# polarshield3_0d.net
KiCad netlist of a schematic drawn in EAGLE
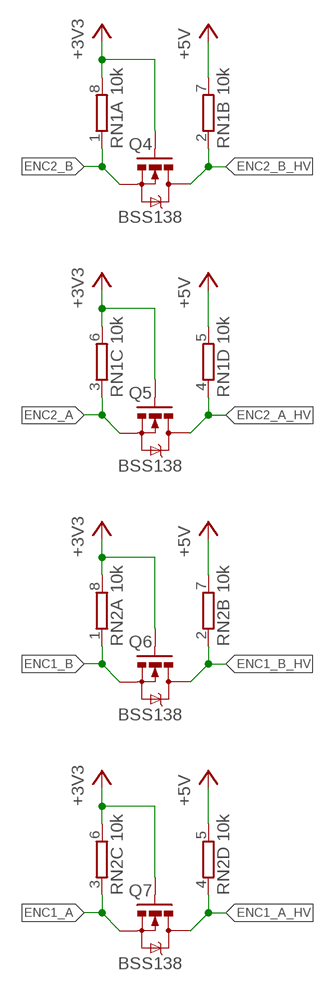
[diagram p0: schematic, sheet 1, part 1 of 2]
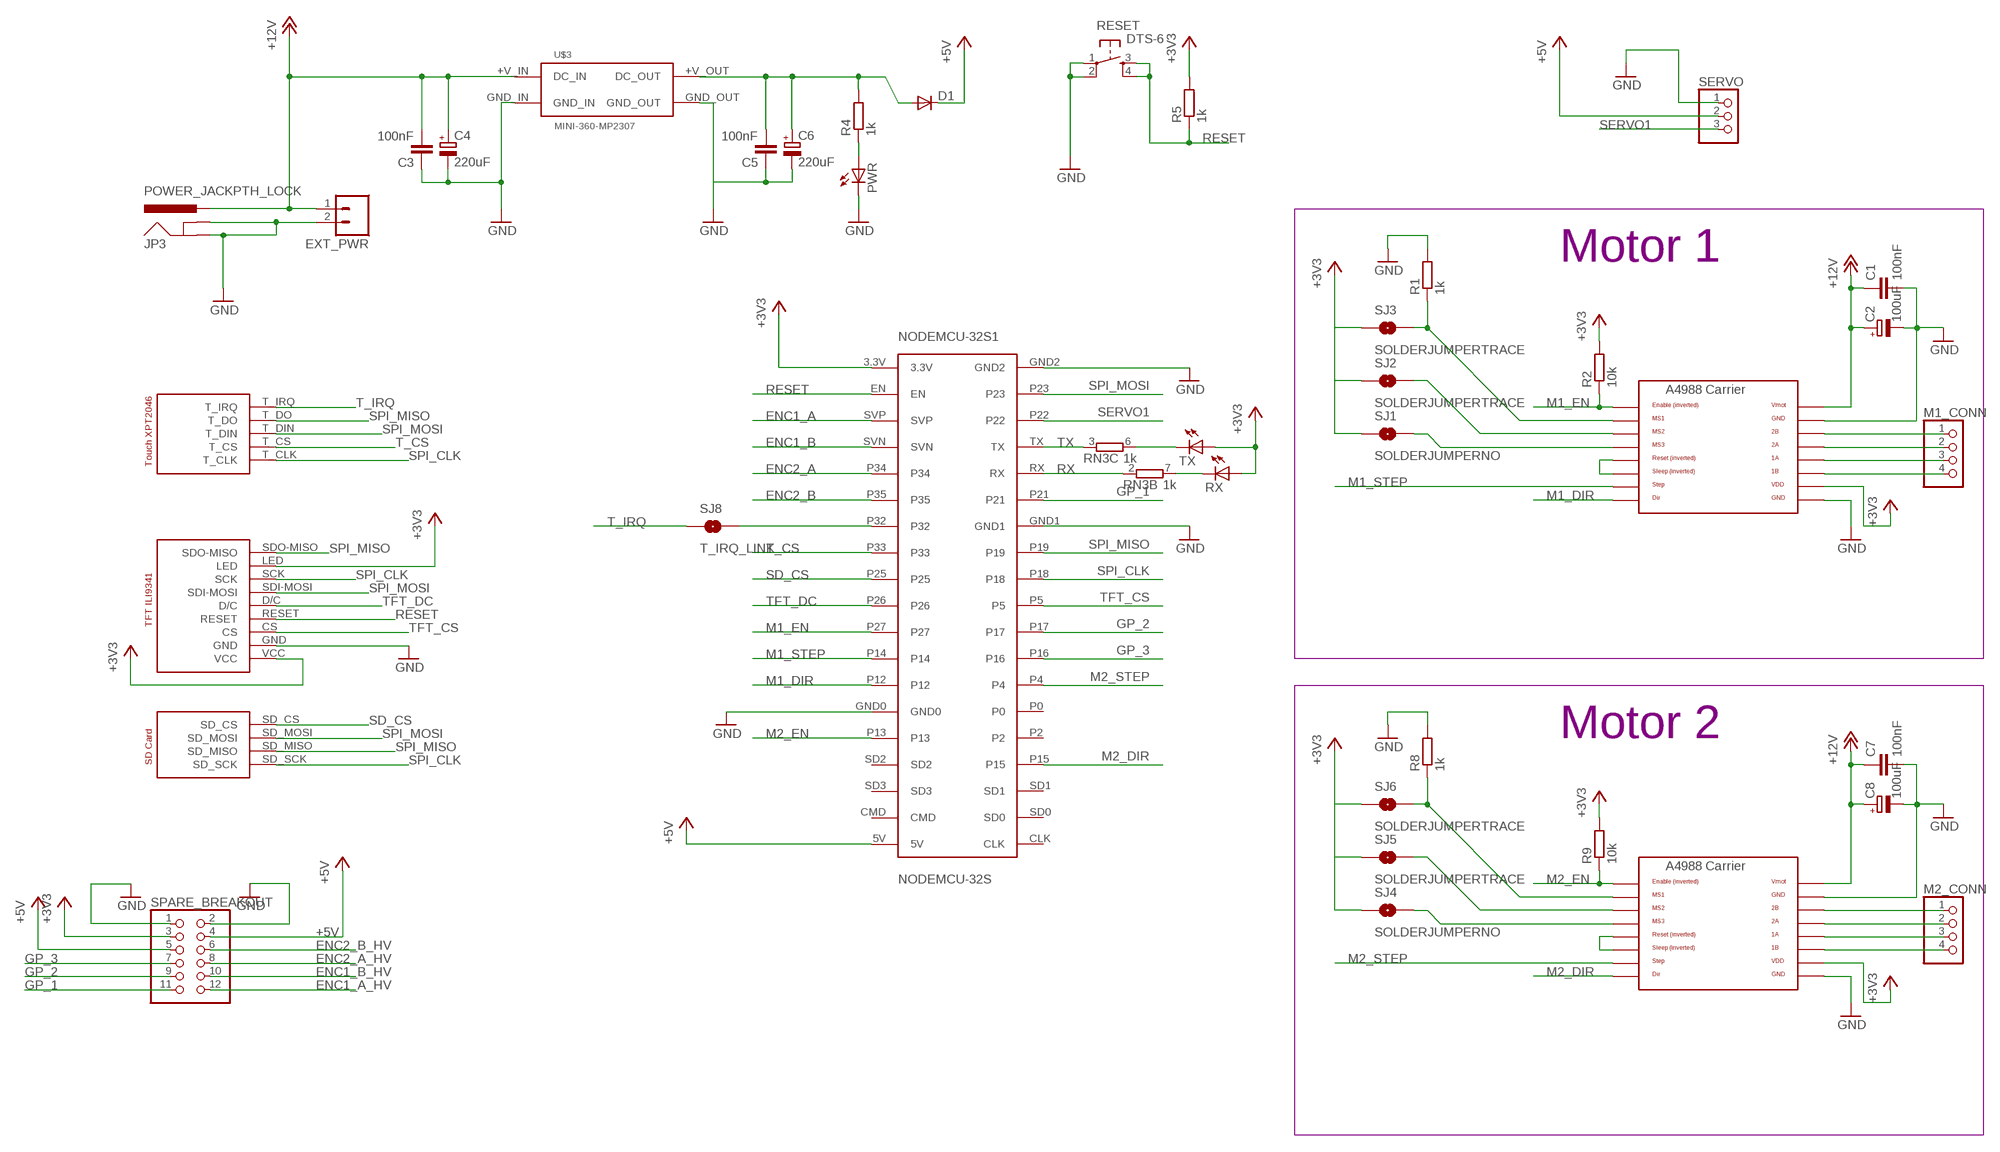
[diagram p1: schematic, sheet 1, part 2 of 2]

(export (version "E")
  (design (tool "Eeschema 10.0.6"))
  (components
    (comp (ref "C1")
      (value "100nF")
      (footprint "eagle-import:C0805")
      (libsource (lib "eagle-import") (part "C-EUC0805"))
    )
    (comp (ref "C2")
      (value "100uF")
      (footprint "eagle-import:153CLV-0605")
      (libsource (lib "eagle-import") (part "CPOL-EU153CLV-0605"))
    )
    (comp (ref "C3")
      (value "100nF")
      (footprint "eagle-import:C0805")
      (libsource (lib "eagle-import") (part "C-EUC0805"))
    )
    (comp (ref "C4")
      (value "220uF")
      (footprint "eagle-import:153CLV-0605")
      (libsource (lib "eagle-import") (part "CPOL-EU153CLV-0605"))
    )
    (comp (ref "C5")
      (value "100nF")
      (footprint "eagle-import:C0805")
      (libsource (lib "eagle-import") (part "C-EUC0805"))
    )
    (comp (ref "C6")
      (value "220uF")
      (footprint "eagle-import:153CLV-0605")
      (libsource (lib "eagle-import") (part "CPOL-EU153CLV-0605"))
    )
    (comp (ref "C7")
      (value "100nF")
      (footprint "eagle-import:C0805")
      (libsource (lib "eagle-import") (part "C-EUC0805"))
    )
    (comp (ref "C8")
      (value "100uF")
      (footprint "eagle-import:153CLV-0605")
      (libsource (lib "eagle-import") (part "CPOL-EU153CLV-0605"))
    )
    (comp (ref "D1")
      (value "DIODE-DO214BA")
      (footprint "eagle-import:DO214BA")
      (libsource (lib "eagle-import") (part "DIODE-DO214BA"))
    )
    (comp (ref "EXT_PWR")
      (value "M02PTH")
      (footprint "eagle-import:1X02")
      (libsource (lib "eagle-import") (part "M02PTH"))
    )
    (comp (ref "JP3")
      (value "POWER_JACKPTH_LOCK")
      (footprint "eagle-import:POWER_JACK_PTH_LOCK")
      (libsource (lib "eagle-import") (part "POWER_JACKPTH_LOCK"))
    )
    (comp (ref "M1_CONN")
      (value "PINHD-1X4/90")
      (footprint "eagle-import:1X04_90")
      (libsource (lib "eagle-import") (part "PINHD-1X4/90"))
    )
    (comp (ref "M2_CONN")
      (value "PINHD-1X4/90")
      (footprint "eagle-import:1X04_90")
      (libsource (lib "eagle-import") (part "PINHD-1X4/90"))
    )
    (comp (ref "MOTOR_1")
      (value "A4988BREAKOUT")
      (footprint "eagle-import:A4988BREAKOUT")
      (libsource (lib "eagle-import") (part "A4988BREAKOUT"))
    )
    (comp (ref "MOTOR_2")
      (value "A4988BREAKOUT")
      (footprint "eagle-import:A4988BREAKOUT")
      (libsource (lib "eagle-import") (part "A4988BREAKOUT"))
    )
    (comp (ref "NODEMCU-32S1")
      (value "NODEMCU-32S")
      (footprint "eagle-import:NODEMCU-32S")
      (libsource (lib "eagle-import") (part "NODEMCU-32S"))
    )
    (comp (ref "PWR")
      (value "LEDCHIPLED_0805")
      (footprint "eagle-import:CHIPLED_0805")
      (libsource (lib "eagle-import") (part "LEDCHIPLED_0805"))
    )
    (comp (ref "Q4")
      (value "BSS138")
      (footprint "eagle-import:SOT23-3")
      (libsource (lib "eagle-import") (part "MOSFET-NCHANNELSMD"))
    )
    (comp (ref "Q5")
      (value "BSS138")
      (footprint "eagle-import:SOT23-3")
      (libsource (lib "eagle-import") (part "MOSFET-NCHANNELSMD"))
    )
    (comp (ref "Q6")
      (value "BSS138")
      (footprint "eagle-import:SOT23-3")
      (libsource (lib "eagle-import") (part "MOSFET-NCHANNELSMD"))
    )
    (comp (ref "Q7")
      (value "BSS138")
      (footprint "eagle-import:SOT23-3")
      (libsource (lib "eagle-import") (part "MOSFET-NCHANNELSMD"))
    )
    (comp (ref "R1")
      (value "1k")
      (footprint "eagle-import:M0805")
      (libsource (lib "eagle-import") (part "R-EU_M0805"))
    )
    (comp (ref "R2")
      (value "10k")
      (footprint "eagle-import:M0805")
      (libsource (lib "eagle-import") (part "R-EU_M0805"))
    )
    (comp (ref "R4")
      (value "1k")
      (footprint "eagle-import:M0805")
      (libsource (lib "eagle-import") (part "R-EU_M0805"))
    )
    (comp (ref "R5")
      (value "1k")
      (footprint "eagle-import:M0805")
      (libsource (lib "eagle-import") (part "R-EU_M0805"))
    )
    (comp (ref "R8")
      (value "1k")
      (footprint "eagle-import:M0805")
      (libsource (lib "eagle-import") (part "R-EU_M0805"))
    )
    (comp (ref "R9")
      (value "10k")
      (footprint "eagle-import:M0805")
      (libsource (lib "eagle-import") (part "R-EU_M0805"))
    )
    (comp (ref "RESET")
      (value "DTS-6")
      (footprint "eagle-import:DTS-6")
      (libsource (lib "eagle-import") (part "DTS-6"))
    )
    (comp (ref "RN1")
      (value "10k")
      (footprint "eagle-import:EXB38V")
      (libsource (lib "eagle-import") (part "4R-NEXB38V"))
    )
    (comp (ref "RN2")
      (value "10k")
      (footprint "eagle-import:EXB38V")
      (libsource (lib "eagle-import") (part "4R-NEXB38V"))
    )
    (comp (ref "RN3")
      (value "1k")
      (footprint "eagle-import:EXB38V")
      (libsource (lib "eagle-import") (part "4R-NEXB38V"))
    )
    (comp (ref "RX")
      (value "LEDCHIPLED_0805")
      (footprint "eagle-import:CHIPLED_0805")
      (libsource (lib "eagle-import") (part "LEDCHIPLED_0805"))
    )
    (comp (ref "SERVO")
      (value "PINHD-1X3/90")
      (footprint "eagle-import:1X03_90")
      (libsource (lib "eagle-import") (part "PINHD-1X3/90"))
    )
    (comp (ref "SJ1")
      (value "SOLDERJUMPERNO")
      (footprint "eagle-import:SJ_2S-NO")
      (libsource (lib "eagle-import") (part "polargraph3_SOLDERJUMPERNO"))
    )
    (comp (ref "SJ2")
      (value "SOLDERJUMPERTRACE")
      (footprint "eagle-import:SJ_2S-TRACE")
      (libsource (lib "eagle-import") (part "polargraph3_SOLDERJUMPERTRACE"))
    )
    (comp (ref "SJ3")
      (value "SOLDERJUMPERTRACE")
      (footprint "eagle-import:SJ_2S-TRACE")
      (libsource (lib "eagle-import") (part "polargraph3_SOLDERJUMPERTRACE"))
    )
    (comp (ref "SJ4")
      (value "SOLDERJUMPERNO")
      (footprint "eagle-import:SJ_2S-NO")
      (libsource (lib "eagle-import") (part "polargraph3_SOLDERJUMPERNO"))
    )
    (comp (ref "SJ5")
      (value "SOLDERJUMPERTRACE")
      (footprint "eagle-import:SJ_2S-TRACE")
      (libsource (lib "eagle-import") (part "polargraph3_SOLDERJUMPERTRACE"))
    )
    (comp (ref "SJ6")
      (value "SOLDERJUMPERTRACE")
      (footprint "eagle-import:SJ_2S-TRACE")
      (libsource (lib "eagle-import") (part "polargraph3_SOLDERJUMPERTRACE"))
    )
    (comp (ref "SJ8")
      (value "T_IRQ_LINK")
      (footprint "eagle-import:SJ_2S-NO")
      (libsource (lib "eagle-import") (part "SOLDERJUMPERNO"))
    )
    (comp (ref "SPARE_BREAKOUT")
      (value "PINHD-2X6")
      (footprint "eagle-import:2X06")
      (libsource (lib "eagle-import") (part "PINHD-2X6"))
    )
    (comp (ref "TX")
      (value "LEDCHIPLED_0805")
      (footprint "eagle-import:CHIPLED_0805")
      (libsource (lib "eagle-import") (part "LEDCHIPLED_0805"))
    )
    (comp (ref "U$2")
      (value "2.4_TFT_SPI_TOUCH_SD")
      (footprint "eagle-import:2.4_TFT_SPI_TOUCH_SD")
      (libsource (lib "eagle-import") (part "2.4_TFT_SPI_TOUCH_SD"))
    )
    (comp (ref "U$3")
      (value "MINI-360-MP2307")
      (footprint "eagle-import:MINI-360-MP2307")
      (libsource (lib "eagle-import") (part "MINI-360-MP2307"))
    )
  )
  (nets
    (net (code "1") (name "+3V3") (class "Default")
      (node (ref "MOTOR_1") (pin "VDD") (pinfunction "VDD_VDD") (pintype "power_in"))
      (node (ref "MOTOR_2") (pin "VDD") (pinfunction "VDD_VDD") (pintype "power_in"))
      (node (ref "NODEMCU-32S1") (pin "3.3V") (pinfunction "3.3V_3.3V") (pintype "bidirectional"))
      (node (ref "Q4") (pin "1") (pinfunction "G_1") (pintype "passive"))
      (node (ref "Q5") (pin "1") (pinfunction "G_1") (pintype "passive"))
      (node (ref "Q6") (pin "1") (pinfunction "G_1") (pintype "passive"))
      (node (ref "Q7") (pin "1") (pinfunction "G_1") (pintype "passive"))
      (node (ref "R2") (pin "2") (pinfunction "2_2") (pintype "passive"))
      (node (ref "R5") (pin "2") (pinfunction "2_2") (pintype "passive"))
      (node (ref "R9") (pin "2") (pinfunction "2_2") (pintype "passive"))
      (node (ref "RN1") (pin "6") (pinfunction "2_6") (pintype "passive"))
      (node (ref "RN1") (pin "8") (pinfunction "2_8") (pintype "passive"))
      (node (ref "RN2") (pin "6") (pinfunction "2_6") (pintype "passive"))
      (node (ref "RN2") (pin "8") (pinfunction "2_8") (pintype "passive"))
      (node (ref "RX") (pin "A") (pinfunction "A_A") (pintype "passive"))
      (node (ref "SJ1") (pin "1") (pinfunction "1_1") (pintype "passive"))
      (node (ref "SJ2") (pin "1") (pinfunction "1_1") (pintype "passive"))
      (node (ref "SJ3") (pin "1") (pinfunction "1_1") (pintype "passive"))
      (node (ref "SJ4") (pin "1") (pinfunction "1_1") (pintype "passive"))
      (node (ref "SJ5") (pin "1") (pinfunction "1_1") (pintype "passive"))
      (node (ref "SJ6") (pin "1") (pinfunction "1_1") (pintype "passive"))
      (node (ref "SPARE_BREAKOUT") (pin "3") (pinfunction "3_3") (pintype "passive"))
      (node (ref "TX") (pin "A") (pinfunction "A_A") (pintype "passive"))
      (node (ref "U$2") (pin "LED") (pinfunction "LED_LED") (pintype "bidirectional"))
      (node (ref "U$2") (pin "VCC") (pinfunction "VCC_VCC") (pintype "bidirectional"))
    )
    (net (code "2") (name "+5V") (class "Default")
      (node (ref "D1") (pin "C") (pinfunction "C_C") (pintype "passive"))
      (node (ref "NODEMCU-32S1") (pin "5V") (pinfunction "5V_5V") (pintype "bidirectional"))
      (node (ref "RN1") (pin "5") (pinfunction "2_5") (pintype "passive"))
      (node (ref "RN1") (pin "7") (pinfunction "2_7") (pintype "passive"))
      (node (ref "RN2") (pin "5") (pinfunction "2_5") (pintype "passive"))
      (node (ref "RN2") (pin "7") (pinfunction "2_7") (pintype "passive"))
      (node (ref "SERVO") (pin "2") (pinfunction "2_2") (pintype "passive"))
      (node (ref "SPARE_BREAKOUT") (pin "4") (pinfunction "4_4") (pintype "passive"))
      (node (ref "SPARE_BREAKOUT") (pin "5") (pinfunction "5_5") (pintype "passive"))
    )
    (net (code "3") (name "+12V") (class "Default")
      (node (ref "C1") (pin "1") (pinfunction "1_1") (pintype "passive"))
      (node (ref "C2") (pin "+") (pinfunction "+_+") (pintype "passive"))
      (node (ref "C3") (pin "2") (pinfunction "2_2") (pintype "passive"))
      (node (ref "C4") (pin "+") (pinfunction "+_+") (pintype "passive"))
      (node (ref "C7") (pin "1") (pinfunction "1_1") (pintype "passive"))
      (node (ref "C8") (pin "+") (pinfunction "+_+") (pintype "passive"))
      (node (ref "EXT_PWR") (pin "1") (pinfunction "1_1") (pintype "passive"))
      (node (ref "JP3") (pin "PWR") (pinfunction "PWR_PWR") (pintype "bidirectional"))
      (node (ref "MOTOR_1") (pin "VMOT") (pinfunction "VMOT_VMOT") (pintype "power_in"))
      (node (ref "MOTOR_2") (pin "VMOT") (pinfunction "VMOT_VMOT") (pintype "power_in"))
      (node (ref "U$3") (pin "+V_IN") (pinfunction "DC_IN_+V_IN") (pintype "bidirectional"))
    )
    (net (code "4") (name "/GP_1") (class "Default")
      (node (ref "NODEMCU-32S1") (pin "P21") (pinfunction "P21_P21") (pintype "bidirectional"))
      (node (ref "SPARE_BREAKOUT") (pin "11") (pinfunction "11_11") (pintype "passive"))
    )
    (net (code "5") (name "/GP_2") (class "Default")
      (node (ref "NODEMCU-32S1") (pin "P17") (pinfunction "P17_P17") (pintype "bidirectional"))
      (node (ref "SPARE_BREAKOUT") (pin "9") (pinfunction "9_9") (pintype "passive"))
    )
    (net (code "6") (name "/GP_3") (class "Default")
      (node (ref "NODEMCU-32S1") (pin "P16") (pinfunction "P16_P16") (pintype "bidirectional"))
      (node (ref "SPARE_BREAKOUT") (pin "7") (pinfunction "7_7") (pintype "passive"))
    )
    (net (code "7") (name "/M1_DIR") (class "Default")
      (node (ref "MOTOR_1") (pin "DIR") (pinfunction "DIR_DIR") (pintype "input"))
      (node (ref "NODEMCU-32S1") (pin "P12") (pinfunction "P12_P12") (pintype "bidirectional"))
    )
    (net (code "8") (name "/M1_EN") (class "Default")
      (node (ref "MOTOR_1") (pin "EN") (pinfunction "EN_EN") (pintype "input"))
      (node (ref "NODEMCU-32S1") (pin "P27") (pinfunction "P27_P27") (pintype "bidirectional"))
      (node (ref "R2") (pin "1") (pinfunction "1_1") (pintype "passive"))
    )
    (net (code "9") (name "/M1_STEP") (class "Default")
      (node (ref "MOTOR_1") (pin "STEP") (pinfunction "STEP_STEP") (pintype "input"))
      (node (ref "NODEMCU-32S1") (pin "P14") (pinfunction "P14_P14") (pintype "bidirectional"))
    )
    (net (code "10") (name "/M2_DIR") (class "Default")
      (node (ref "MOTOR_2") (pin "DIR") (pinfunction "DIR_DIR") (pintype "input"))
      (node (ref "NODEMCU-32S1") (pin "P15") (pinfunction "P15_P15") (pintype "bidirectional"))
    )
    (net (code "11") (name "/M2_EN") (class "Default")
      (node (ref "MOTOR_2") (pin "EN") (pinfunction "EN_EN") (pintype "input"))
      (node (ref "NODEMCU-32S1") (pin "P13") (pinfunction "P13_P13") (pintype "bidirectional"))
      (node (ref "R9") (pin "1") (pinfunction "1_1") (pintype "passive"))
    )
    (net (code "12") (name "/M2_STEP") (class "Default")
      (node (ref "MOTOR_2") (pin "STEP") (pinfunction "STEP_STEP") (pintype "input"))
      (node (ref "NODEMCU-32S1") (pin "P4") (pinfunction "P4_P4") (pintype "bidirectional"))
    )
    (net (code "13") (name "/RESET") (class "Default")
      (node (ref "NODEMCU-32S1") (pin "EN") (pinfunction "EN_EN") (pintype "bidirectional"))
      (node (ref "R5") (pin "1") (pinfunction "1_1") (pintype "passive"))
      (node (ref "RESET") (pin "3") (pinfunction "3_3") (pintype "passive"))
      (node (ref "RESET") (pin "4") (pinfunction "4_4") (pintype "passive"))
      (node (ref "U$2") (pin "RESET") (pinfunction "RESET_RESET") (pintype "bidirectional"))
    )
    (net (code "14") (name "/RX") (class "Default")
      (node (ref "NODEMCU-32S1") (pin "RX") (pinfunction "RX_RX") (pintype "bidirectional"))
      (node (ref "RN3") (pin "2") (pinfunction "1_2") (pintype "passive"))
    )
    (net (code "15") (name "/SD_CS") (class "Default")
      (node (ref "NODEMCU-32S1") (pin "P25") (pinfunction "P25_P25") (pintype "bidirectional"))
      (node (ref "U$2") (pin "SD_CS") (pinfunction "SD_CS_SD_CS") (pintype "bidirectional"))
    )
    (net (code "16") (name "/SERVO1") (class "Default")
      (node (ref "NODEMCU-32S1") (pin "P22") (pinfunction "P22_P22") (pintype "bidirectional"))
      (node (ref "SERVO") (pin "3") (pinfunction "3_3") (pintype "passive"))
    )
    (net (code "17") (name "/SPI_CLK") (class "Default")
      (node (ref "NODEMCU-32S1") (pin "P18") (pinfunction "P18_P18") (pintype "bidirectional"))
      (node (ref "U$2") (pin "SCK") (pinfunction "SCK_SCK") (pintype "bidirectional"))
      (node (ref "U$2") (pin "SD_SCK") (pinfunction "SD_SCK_SD_SCK") (pintype "bidirectional"))
      (node (ref "U$2") (pin "T_CLK") (pinfunction "T_CLK_T_CLK") (pintype "input"))
    )
    (net (code "18") (name "/SPI_MISO") (class "Default")
      (node (ref "NODEMCU-32S1") (pin "P19") (pinfunction "P19_P19") (pintype "bidirectional"))
      (node (ref "U$2") (pin "SDO-MISO") (pinfunction "SDO-MISO_SDO-MISO") (pintype "bidirectional"))
      (node (ref "U$2") (pin "SD_MISO") (pinfunction "SD_MISO_SD_MISO") (pintype "bidirectional"))
      (node (ref "U$2") (pin "T_DO") (pinfunction "T_DO_T_DO") (pintype "output"))
    )
    (net (code "19") (name "/SPI_MOSI") (class "Default")
      (node (ref "NODEMCU-32S1") (pin "P23") (pinfunction "P23_P23") (pintype "bidirectional"))
      (node (ref "U$2") (pin "SDI-MOSI") (pinfunction "SDI-MOSI_SDI-MOSI") (pintype "bidirectional"))
      (node (ref "U$2") (pin "SD_MOSI") (pinfunction "SD_MOSI_SD_MOSI") (pintype "bidirectional"))
      (node (ref "U$2") (pin "T_DIN") (pinfunction "T_DIN_T_DIN") (pintype "input"))
    )
    (net (code "20") (name "/TFT_CS") (class "Default")
      (node (ref "NODEMCU-32S1") (pin "P5") (pinfunction "P5_P5") (pintype "bidirectional"))
      (node (ref "U$2") (pin "CS") (pinfunction "CS_CS") (pintype "bidirectional"))
    )
    (net (code "21") (name "/TFT_DC") (class "Default")
      (node (ref "NODEMCU-32S1") (pin "P26") (pinfunction "P26_P26") (pintype "bidirectional"))
      (node (ref "U$2") (pin "D/C") (pinfunction "D/C_D/C") (pintype "bidirectional"))
    )
    (net (code "22") (name "/TX") (class "Default")
      (node (ref "NODEMCU-32S1") (pin "TX") (pinfunction "TX_TX") (pintype "bidirectional"))
      (node (ref "RN3") (pin "3") (pinfunction "1_3") (pintype "passive"))
    )
    (net (code "23") (name "/T_CS") (class "Default")
      (node (ref "NODEMCU-32S1") (pin "P33") (pinfunction "P33_P33") (pintype "bidirectional"))
      (node (ref "U$2") (pin "T_CS") (pinfunction "T_CS_T_CS") (pintype "output"))
    )
    (net (code "24") (name "/T_IRQ") (class "Default")
      (node (ref "SJ8") (pin "1") (pinfunction "1_1") (pintype "passive"))
      (node (ref "U$2") (pin "T_IRQ") (pinfunction "T_IRQ_T_IRQ") (pintype "output"))
    )
    (net (code "25") (name "ENC1_A") (class "Default")
      (node (ref "NODEMCU-32S1") (pin "SVP") (pinfunction "SVP_SVP") (pintype "bidirectional"))
      (node (ref "Q7") (pin "2") (pinfunction "S_2") (pintype "passive"))
      (node (ref "RN2") (pin "3") (pinfunction "1_3") (pintype "passive"))
    )
    (net (code "26") (name "ENC1_A_HV") (class "Default")
      (node (ref "Q7") (pin "3") (pinfunction "D_3") (pintype "passive"))
      (node (ref "RN2") (pin "4") (pinfunction "1_4") (pintype "passive"))
      (node (ref "SPARE_BREAKOUT") (pin "12") (pinfunction "12_12") (pintype "passive"))
    )
    (net (code "27") (name "ENC1_B") (class "Default")
      (node (ref "NODEMCU-32S1") (pin "SVN") (pinfunction "SVN_SVN") (pintype "bidirectional"))
      (node (ref "Q6") (pin "2") (pinfunction "S_2") (pintype "passive"))
      (node (ref "RN2") (pin "1") (pinfunction "1_1") (pintype "passive"))
    )
    (net (code "28") (name "ENC1_B_HV") (class "Default")
      (node (ref "Q6") (pin "3") (pinfunction "D_3") (pintype "passive"))
      (node (ref "RN2") (pin "2") (pinfunction "1_2") (pintype "passive"))
      (node (ref "SPARE_BREAKOUT") (pin "10") (pinfunction "10_10") (pintype "passive"))
    )
    (net (code "29") (name "ENC2_A") (class "Default")
      (node (ref "NODEMCU-32S1") (pin "P34") (pinfunction "P34_P34") (pintype "bidirectional"))
      (node (ref "Q5") (pin "2") (pinfunction "S_2") (pintype "passive"))
      (node (ref "RN1") (pin "3") (pinfunction "1_3") (pintype "passive"))
    )
    (net (code "30") (name "ENC2_A_HV") (class "Default")
      (node (ref "Q5") (pin "3") (pinfunction "D_3") (pintype "passive"))
      (node (ref "RN1") (pin "4") (pinfunction "1_4") (pintype "passive"))
      (node (ref "SPARE_BREAKOUT") (pin "8") (pinfunction "8_8") (pintype "passive"))
    )
    (net (code "31") (name "ENC2_B") (class "Default")
      (node (ref "NODEMCU-32S1") (pin "P35") (pinfunction "P35_P35") (pintype "bidirectional"))
      (node (ref "Q4") (pin "2") (pinfunction "S_2") (pintype "passive"))
      (node (ref "RN1") (pin "1") (pinfunction "1_1") (pintype "passive"))
    )
    (net (code "32") (name "ENC2_B_HV") (class "Default")
      (node (ref "Q4") (pin "3") (pinfunction "D_3") (pintype "passive"))
      (node (ref "RN1") (pin "2") (pinfunction "1_2") (pintype "passive"))
      (node (ref "SPARE_BREAKOUT") (pin "6") (pinfunction "6_6") (pintype "passive"))
    )
    (net (code "33") (name "GND") (class "Default")
      (node (ref "C1") (pin "2") (pinfunction "2_2") (pintype "passive"))
      (node (ref "C2") (pin "-") (pinfunction "-_-") (pintype "passive"))
      (node (ref "C3") (pin "1") (pinfunction "1_1") (pintype "passive"))
      (node (ref "C4") (pin "-") (pinfunction "-_-") (pintype "passive"))
      (node (ref "C5") (pin "1") (pinfunction "1_1") (pintype "passive"))
      (node (ref "C6") (pin "-") (pinfunction "-_-") (pintype "passive"))
      (node (ref "C7") (pin "2") (pinfunction "2_2") (pintype "passive"))
      (node (ref "C8") (pin "-") (pinfunction "-_-") (pintype "passive"))
      (node (ref "EXT_PWR") (pin "2") (pinfunction "2_2") (pintype "passive"))
      (node (ref "JP3") (pin "GND") (pinfunction "GND_GND") (pintype "bidirectional"))
      (node (ref "JP3") (pin "GNDBREAK") (pinfunction "GNDBREAK_GNDBREAK") (pintype "bidirectional"))
      (node (ref "MOTOR_1") (pin "GND") (pinfunction "GND_GND") (pintype "power_in"))
      (node (ref "MOTOR_1") (pin "GND@0") (pinfunction "GND_GND@0") (pintype "power_in"))
      (node (ref "MOTOR_2") (pin "GND") (pinfunction "GND_GND") (pintype "power_in"))
      (node (ref "MOTOR_2") (pin "GND@0") (pinfunction "GND_GND@0") (pintype "power_in"))
      (node (ref "NODEMCU-32S1") (pin "GND0") (pinfunction "GND0_GND0") (pintype "bidirectional"))
      (node (ref "NODEMCU-32S1") (pin "GND1") (pinfunction "GND1_GND1") (pintype "bidirectional"))
      (node (ref "NODEMCU-32S1") (pin "GND2") (pinfunction "GND2_GND2") (pintype "bidirectional"))
      (node (ref "PWR") (pin "C") (pinfunction "C_C") (pintype "passive"))
      (node (ref "R1") (pin "2") (pinfunction "2_2") (pintype "passive"))
      (node (ref "R8") (pin "2") (pinfunction "2_2") (pintype "passive"))
      (node (ref "RESET") (pin "1") (pinfunction "1_1") (pintype "passive"))
      (node (ref "RESET") (pin "2") (pinfunction "2_2") (pintype "passive"))
      (node (ref "SERVO") (pin "1") (pinfunction "1_1") (pintype "passive"))
      (node (ref "SPARE_BREAKOUT") (pin "1") (pinfunction "1_1") (pintype "passive"))
      (node (ref "SPARE_BREAKOUT") (pin "2") (pinfunction "2_2") (pintype "passive"))
      (node (ref "U$2") (pin "GND") (pinfunction "GND_GND") (pintype "bidirectional"))
      (node (ref "U$3") (pin "GND_IN") (pinfunction "GND_IN_GND_IN") (pintype "bidirectional"))
      (node (ref "U$3") (pin "GND_OUT") (pinfunction "GND_OUT_GND_OUT") (pintype "bidirectional"))
    )
    (net (code "34") (name "Net-(M1_CONN-Pad1)") (class "Default")
      (node (ref "M1_CONN") (pin "1") (pinfunction "1_1") (pintype "passive"))
      (node (ref "MOTOR_1") (pin "2B") (pinfunction "2B_2B") (pintype "output"))
    )
    (net (code "35") (name "Net-(M1_CONN-Pad2)") (class "Default")
      (node (ref "M1_CONN") (pin "2") (pinfunction "2_2") (pintype "passive"))
      (node (ref "MOTOR_1") (pin "2A") (pinfunction "2A_2A") (pintype "output"))
    )
    (net (code "36") (name "Net-(M1_CONN-Pad3)") (class "Default")
      (node (ref "M1_CONN") (pin "3") (pinfunction "3_3") (pintype "passive"))
      (node (ref "MOTOR_1") (pin "1A") (pinfunction "1A_1A") (pintype "output"))
    )
    (net (code "37") (name "Net-(M1_CONN-Pad4)") (class "Default")
      (node (ref "M1_CONN") (pin "4") (pinfunction "4_4") (pintype "passive"))
      (node (ref "MOTOR_1") (pin "1B") (pinfunction "1B_1B") (pintype "output"))
    )
    (net (code "38") (name "Net-(M2_CONN-Pad1)") (class "Default")
      (node (ref "M2_CONN") (pin "1") (pinfunction "1_1") (pintype "passive"))
      (node (ref "MOTOR_2") (pin "2B") (pinfunction "2B_2B") (pintype "output"))
    )
    (net (code "39") (name "Net-(M2_CONN-Pad2)") (class "Default")
      (node (ref "M2_CONN") (pin "2") (pinfunction "2_2") (pintype "passive"))
      (node (ref "MOTOR_2") (pin "2A") (pinfunction "2A_2A") (pintype "output"))
    )
    (net (code "40") (name "Net-(M2_CONN-Pad3)") (class "Default")
      (node (ref "M2_CONN") (pin "3") (pinfunction "3_3") (pintype "passive"))
      (node (ref "MOTOR_2") (pin "1A") (pinfunction "1A_1A") (pintype "output"))
    )
    (net (code "41") (name "Net-(M2_CONN-Pad4)") (class "Default")
      (node (ref "M2_CONN") (pin "4") (pinfunction "4_4") (pintype "passive"))
      (node (ref "MOTOR_2") (pin "1B") (pinfunction "1B_1B") (pintype "output"))
    )
    (net (code "42") (name "Net-(MOTOR_1-PadMS1)") (class "Default")
      (node (ref "MOTOR_1") (pin "MS1") (pinfunction "MS1_MS1") (pintype "input"))
      (node (ref "R1") (pin "1") (pinfunction "1_1") (pintype "passive"))
      (node (ref "SJ3") (pin "2") (pinfunction "2_2") (pintype "passive"))
    )
    (net (code "43") (name "Net-(MOTOR_1-PadMS2)") (class "Default")
      (node (ref "MOTOR_1") (pin "MS2") (pinfunction "MS2_MS2") (pintype "input"))
      (node (ref "SJ2") (pin "2") (pinfunction "2_2") (pintype "passive"))
    )
    (net (code "44") (name "Net-(MOTOR_1-PadMS3)") (class "Default")
      (node (ref "MOTOR_1") (pin "MS3") (pinfunction "MS3_MS3") (pintype "input"))
      (node (ref "SJ1") (pin "2") (pinfunction "2_2") (pintype "passive"))
    )
    (net (code "45") (name "Net-(MOTOR_1-SLEEP)") (class "Default")
      (node (ref "MOTOR_1") (pin "RST") (pinfunction "RST_RST") (pintype "input"))
      (node (ref "MOTOR_1") (pin "SLP") (pinfunction "SLEEP_SLP") (pintype "input"))
    )
    (net (code "46") (name "Net-(MOTOR_2-PadMS1)") (class "Default")
      (node (ref "MOTOR_2") (pin "MS1") (pinfunction "MS1_MS1") (pintype "input"))
      (node (ref "R8") (pin "1") (pinfunction "1_1") (pintype "passive"))
      (node (ref "SJ6") (pin "2") (pinfunction "2_2") (pintype "passive"))
    )
    (net (code "47") (name "Net-(MOTOR_2-PadMS2)") (class "Default")
      (node (ref "MOTOR_2") (pin "MS2") (pinfunction "MS2_MS2") (pintype "input"))
      (node (ref "SJ5") (pin "2") (pinfunction "2_2") (pintype "passive"))
    )
    (net (code "48") (name "Net-(MOTOR_2-PadMS3)") (class "Default")
      (node (ref "MOTOR_2") (pin "MS3") (pinfunction "MS3_MS3") (pintype "input"))
      (node (ref "SJ4") (pin "2") (pinfunction "2_2") (pintype "passive"))
    )
    (net (code "49") (name "Net-(MOTOR_2-SLEEP)") (class "Default")
      (node (ref "MOTOR_2") (pin "RST") (pinfunction "RST_RST") (pintype "input"))
      (node (ref "MOTOR_2") (pin "SLP") (pinfunction "SLEEP_SLP") (pintype "input"))
    )
    (net (code "50") (name "Net-(NODEMCU-32S1-PadP32)") (class "Default")
      (node (ref "NODEMCU-32S1") (pin "P32") (pinfunction "P32_P32") (pintype "bidirectional"))
      (node (ref "SJ8") (pin "2") (pinfunction "2_2") (pintype "passive"))
    )
    (net (code "51") (name "Net-(PWR-PadA)") (class "Default")
      (node (ref "PWR") (pin "A") (pinfunction "A_A") (pintype "passive"))
      (node (ref "R4") (pin "1") (pinfunction "1_1") (pintype "passive"))
    )
    (net (code "52") (name "Net-(RN3B-2)") (class "Default")
      (node (ref "RN3") (pin "7") (pinfunction "2_7") (pintype "passive"))
      (node (ref "RX") (pin "C") (pinfunction "C_C") (pintype "passive"))
    )
    (net (code "53") (name "Net-(RN3C-2)") (class "Default")
      (node (ref "RN3") (pin "6") (pinfunction "2_6") (pintype "passive"))
      (node (ref "TX") (pin "C") (pinfunction "C_C") (pintype "passive"))
    )
    (net (code "54") (name "Net-(U$3-DC_OUT)") (class "Default")
      (node (ref "C5") (pin "2") (pinfunction "2_2") (pintype "passive"))
      (node (ref "C6") (pin "+") (pinfunction "+_+") (pintype "passive"))
      (node (ref "D1") (pin "A") (pinfunction "A_A") (pintype "passive"))
      (node (ref "R4") (pin "2") (pinfunction "2_2") (pintype "passive"))
      (node (ref "U$3") (pin "+V_OUT") (pinfunction "DC_OUT_+V_OUT") (pintype "bidirectional"))
    )
    (net (code "55") (name "unconnected-(NODEMCU-32S1-PadCLK)") (class "Default")
      (node (ref "NODEMCU-32S1") (pin "CLK") (pinfunction "CLK_CLK") (pintype "bidirectional"))
    )
    (net (code "56") (name "unconnected-(NODEMCU-32S1-PadCMD)") (class "Default")
      (node (ref "NODEMCU-32S1") (pin "CMD") (pinfunction "CMD_CMD") (pintype "bidirectional"))
    )
    (net (code "57") (name "unconnected-(NODEMCU-32S1-PadP0)") (class "Default")
      (node (ref "NODEMCU-32S1") (pin "P0") (pinfunction "P0_P0") (pintype "bidirectional"))
    )
    (net (code "58") (name "unconnected-(NODEMCU-32S1-PadP2)") (class "Default")
      (node (ref "NODEMCU-32S1") (pin "P2") (pinfunction "P2_P2") (pintype "bidirectional"))
    )
    (net (code "59") (name "unconnected-(NODEMCU-32S1-PadSD0)") (class "Default")
      (node (ref "NODEMCU-32S1") (pin "SD0") (pinfunction "SD0_SD0") (pintype "bidirectional"))
    )
    (net (code "60") (name "unconnected-(NODEMCU-32S1-PadSD1)") (class "Default")
      (node (ref "NODEMCU-32S1") (pin "SD1") (pinfunction "SD1_SD1") (pintype "bidirectional"))
    )
    (net (code "61") (name "unconnected-(NODEMCU-32S1-PadSD2)") (class "Default")
      (node (ref "NODEMCU-32S1") (pin "SD2") (pinfunction "SD2_SD2") (pintype "bidirectional"))
    )
    (net (code "62") (name "unconnected-(NODEMCU-32S1-PadSD3)") (class "Default")
      (node (ref "NODEMCU-32S1") (pin "SD3") (pinfunction "SD3_SD3") (pintype "bidirectional"))
    )
  )
)
